# 12-Power.net
KiCad netlist of a schematic drawn in Altium Designer
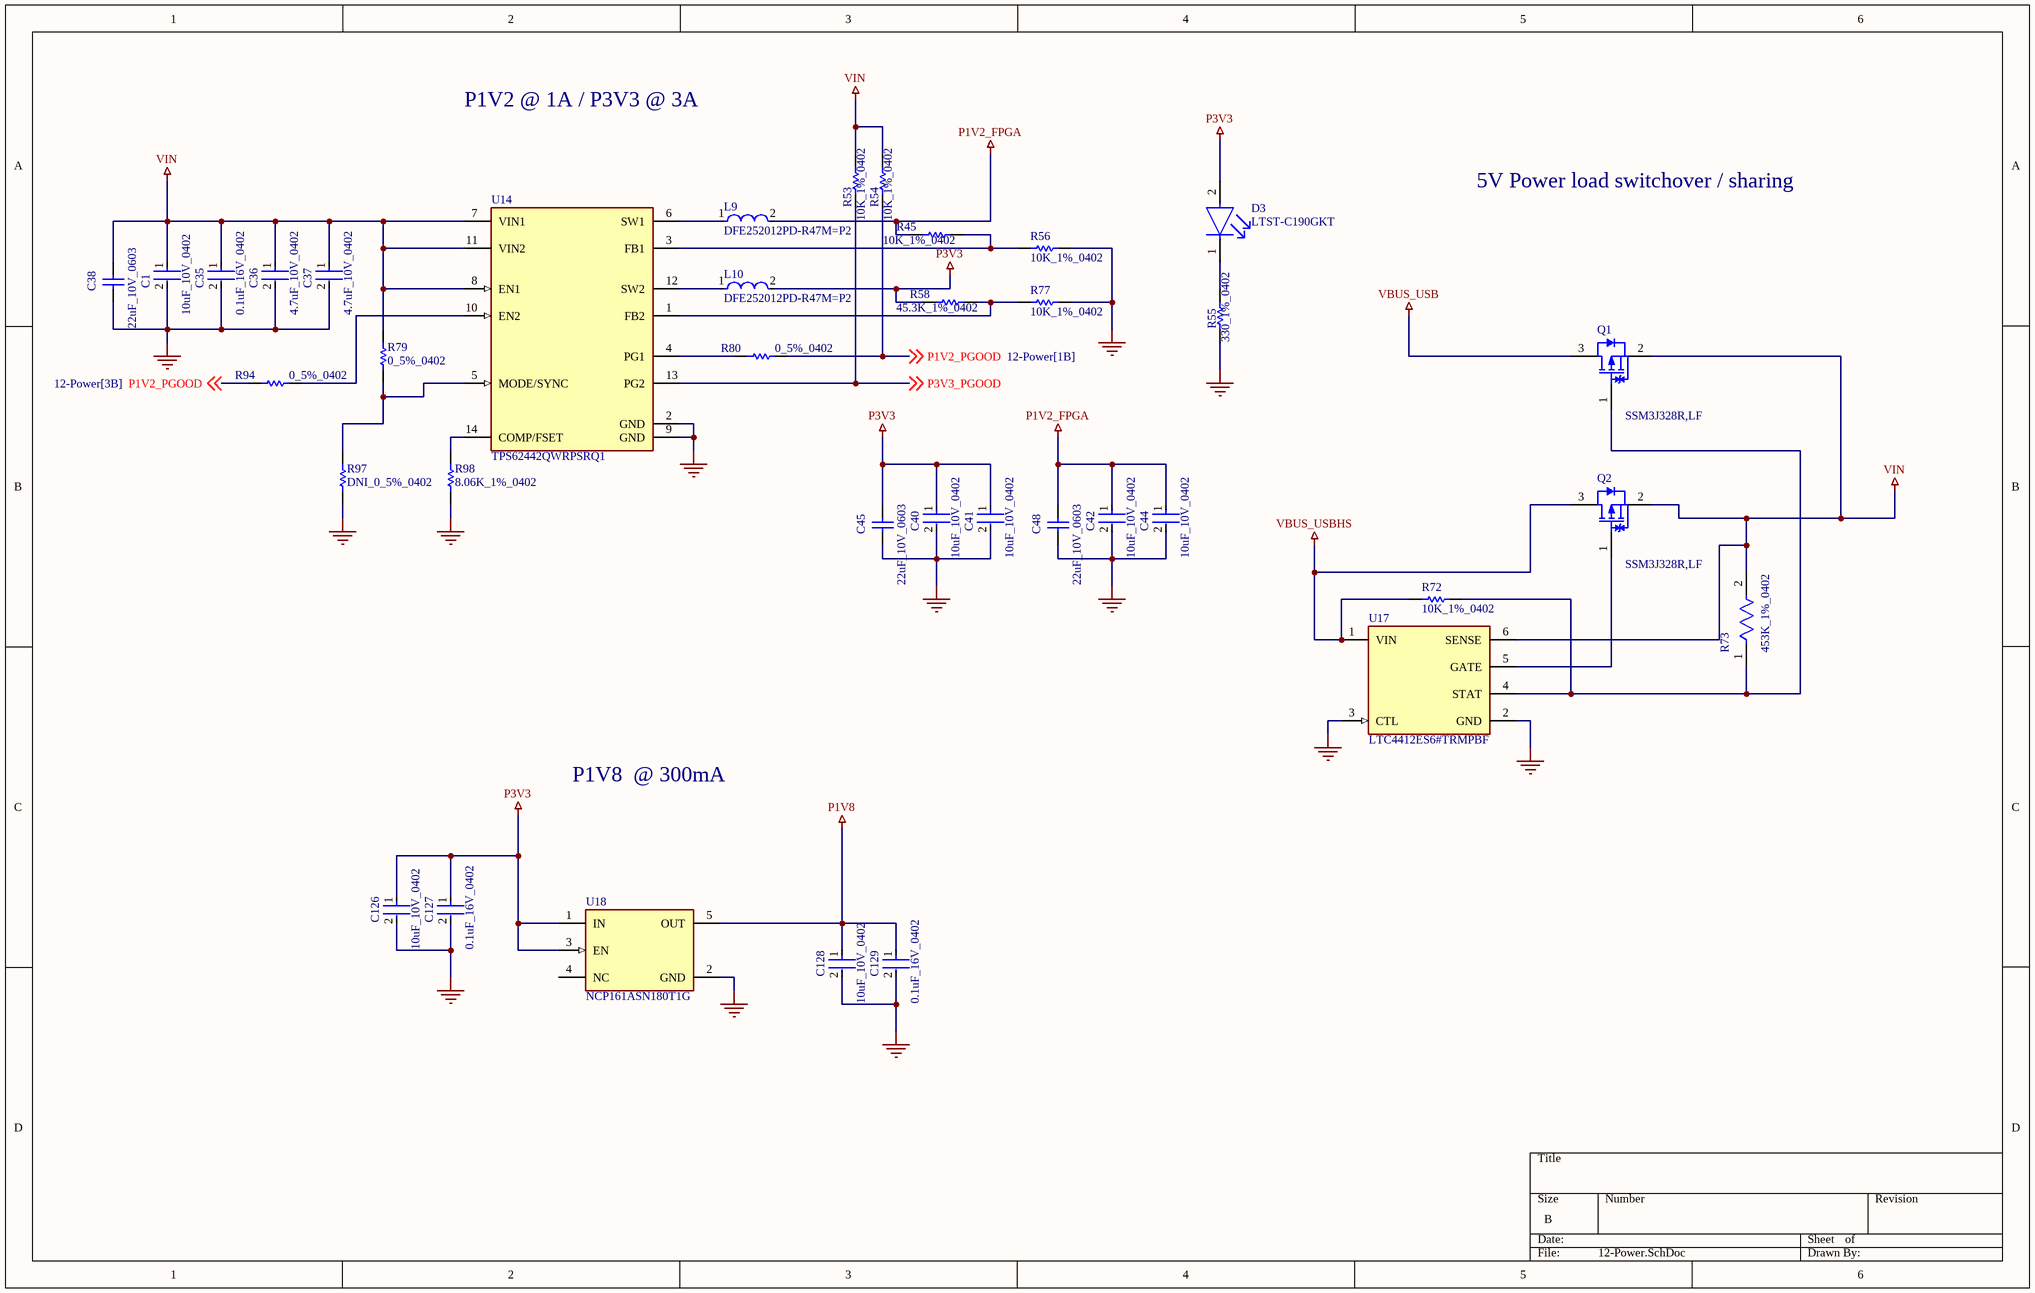
[diagram p0: 12-Power.SchDoc]

(export (version "E")
  (design (tool "Eeschema 10.0.6"))
  (components
    (comp (ref "C1")
      (value "10uF_10V_0402")
      (footprint "FP-CL05A106MP5NUNC-MFG")
      (description "CAP CER 10UF 10V X5R 0402")
      (fields
        (field (name "OCTOPART") "https://octopart.com/cl05a106mp5nunc-samsung-22457395")
        (field (name "TOLERANCE") "20%")
      )
      (libsource (lib "Altium Content Vault") (part "b4654b650e69147ec39a6b967a45e02"))
    )
    (comp (ref "C35")
      (value "0.1uF_16V_0402")
      (footprint "FP-C0402-BB-MFG")
      (description "CAP CER 0.1UF 16V 5% X7R 0402")
      (fields
        (field (name "MANUFACTURER") "Kemet")
        (field (name "MANUFACTURER PART NUMBER") "C0402C104J4RACTU")
      )
      (libsource (lib "Altium Content Vault") (part "b4654b650e69147ec39a6b967a45e02"))
    )
    (comp (ref "C36")
      (value "4.7uF_10V_0402")
      (footprint "FP-C1005-050-0_15-MFG")
      (description "CAP CER 4.7UF 10V X5R 0402")
      (fields (field (name "TOLERANCE") "10%"))
      (libsource (lib "Altium Content Vault") (part "b4654b650e69147ec39a6b967a45e02"))
    )
    (comp (ref "C37")
      (value "4.7uF_10V_0402")
      (footprint "FP-C1005-050-0_15-MFG")
      (description "CAP CER 4.7UF 10V X5R 0402")
      (fields (field (name "TOLERANCE") "10%"))
      (libsource (lib "Altium Content Vault") (part "b4654b650e69147ec39a6b967a45e02"))
    )
    (comp (ref "C38")
      (value "22uF_10V_0603")
      (footprint "CAPC1608X100X20ML10")
      (description "Chip Capacitor, 22 uF, +/- 20%, 10 V, -55 to 85 degC, 0603 (1608 Metric), RoHS, Tape and Reel")
      (fields (field (name "MANUFACTURER") "TDK") (field (name "TOLERANCE") "±20%"))
      (libsource (lib "Altium Content Vault") (part "CAP-NP-2"))
    )
    (comp (ref "C40")
      (value "10uF_10V_0402")
      (footprint "FP-CL05A106MP5NUNC-MFG")
      (description "CAP CER 10UF 10V X5R 0402")
      (fields
        (field (name "OCTOPART") "https://octopart.com/cl05a106mp5nunc-samsung-22457395")
        (field (name "TOLERANCE") "20%")
      )
      (libsource (lib "Altium Content Vault") (part "b4654b650e69147ec39a6b967a45e02"))
    )
    (comp (ref "C41")
      (value "10uF_10V_0402")
      (footprint "FP-CL05A106MP5NUNC-MFG")
      (description "CAP CER 10UF 10V X5R 0402")
      (fields
        (field (name "OCTOPART") "https://octopart.com/cl05a106mp5nunc-samsung-22457395")
        (field (name "TOLERANCE") "20%")
      )
      (libsource (lib "Altium Content Vault") (part "b4654b650e69147ec39a6b967a45e02"))
    )
    (comp (ref "C42")
      (value "10uF_10V_0402")
      (footprint "FP-CL05A106MP5NUNC-MFG")
      (description "CAP CER 10UF 10V X5R 0402")
      (fields
        (field (name "OCTOPART") "https://octopart.com/cl05a106mp5nunc-samsung-22457395")
        (field (name "TOLERANCE") "20%")
      )
      (libsource (lib "Altium Content Vault") (part "b4654b650e69147ec39a6b967a45e02"))
    )
    (comp (ref "C44")
      (value "10uF_10V_0402")
      (footprint "FP-CL05A106MP5NUNC-MFG")
      (description "CAP CER 10UF 10V X5R 0402")
      (fields
        (field (name "OCTOPART") "https://octopart.com/cl05a106mp5nunc-samsung-22457395")
        (field (name "TOLERANCE") "20%")
      )
      (libsource (lib "Altium Content Vault") (part "b4654b650e69147ec39a6b967a45e02"))
    )
    (comp (ref "C45")
      (value "22uF_10V_0603")
      (footprint "CAPC1608X100X20ML10")
      (description "Chip Capacitor, 22 uF, +/- 20%, 10 V, -55 to 85 degC, 0603 (1608 Metric), RoHS, Tape and Reel")
      (fields (field (name "MANUFACTURER") "TDK") (field (name "TOLERANCE") "±20%"))
      (libsource (lib "Altium Content Vault") (part "CAP-NP-2"))
    )
    (comp (ref "C48")
      (value "22uF_10V_0603")
      (footprint "CAPC1608X100X20ML10")
      (description "Chip Capacitor, 22 uF, +/- 20%, 10 V, -55 to 85 degC, 0603 (1608 Metric), RoHS, Tape and Reel")
      (fields (field (name "MANUFACTURER") "TDK") (field (name "TOLERANCE") "±20%"))
      (libsource (lib "Altium Content Vault") (part "CAP-NP-2"))
    )
    (comp (ref "C126")
      (value "10uF_10V_0402")
      (footprint "FP-CL05A106MP5NUNC-MFG")
      (description "CAP CER 10UF 10V X5R 0402")
      (fields
        (field (name "OCTOPART") "https://octopart.com/cl05a106mp5nunc-samsung-22457395")
        (field (name "TOLERANCE") "20%")
      )
      (libsource (lib "Altium Content Vault") (part "b4654b650e69147ec39a6b967a45e02"))
    )
    (comp (ref "C127")
      (value "0.1uF_16V_0402")
      (footprint "FP-C0402-BB-MFG")
      (description "CAP CER 0.1UF 16V 5% X7R 0402")
      (fields
        (field (name "MANUFACTURER") "Kemet")
        (field (name "MANUFACTURER PART NUMBER") "C0402C104J4RACTU")
      )
      (libsource (lib "Altium Content Vault") (part "b4654b650e69147ec39a6b967a45e02"))
    )
    (comp (ref "C128")
      (value "10uF_10V_0402")
      (footprint "FP-CL05A106MP5NUNC-MFG")
      (description "CAP CER 10UF 10V X5R 0402")
      (fields
        (field (name "OCTOPART") "https://octopart.com/cl05a106mp5nunc-samsung-22457395")
        (field (name "TOLERANCE") "20%")
      )
      (libsource (lib "Altium Content Vault") (part "b4654b650e69147ec39a6b967a45e02"))
    )
    (comp (ref "C129")
      (value "0.1uF_16V_0402")
      (footprint "FP-C0402-BB-MFG")
      (description "CAP CER 0.1UF 16V 5% X7R 0402")
      (fields
        (field (name "MANUFACTURER") "Kemet")
        (field (name "MANUFACTURER PART NUMBER") "C0402C104J4RACTU")
      )
      (libsource (lib "Altium Content Vault") (part "b4654b650e69147ec39a6b967a45e02"))
    )
    (comp (ref "D3")
      (value "LTST-C190GKT")
      (footprint "FP-LTST-C190GKT-MFG")
      (description "LED GREEN CLEAR CHIP SMD")
      (fields (field (name "VOLTAGE") "2V"))
      (libsource (lib "Altium Content Vault") (part "8706943c75ba83719d021d2fdc84c58"))
    )
    (comp (ref "L9")
      (value "DFE252012PD-R47M=P2")
      (footprint "FP-DFE252012C-IPC_A")
      (description "Shielded Wirewound Inductor 0.47uH 20% 4000mA 0.027Ω 1008 (2520)")
      (libsource (lib "Altium Content Vault") (part "725321dda6339637d4d059423bc1c3c"))
    )
    (comp (ref "L10")
      (value "DFE252012PD-R47M=P2")
      (footprint "FP-DFE252012C-IPC_A")
      (description "Shielded Wirewound Inductor 0.47uH 20% 4000mA 0.027Ω 1008 (2520)")
      (libsource (lib "Altium Content Vault") (part "725321dda6339637d4d059423bc1c3c"))
    )
    (comp (ref "Q1")
      (value "SSM3J328R,LF")
      (footprint "TOSH-SOT-23F_V")
      (fields (field (name "MANUFACTURER") "Toshiba"))
      (libsource (lib "Altium Content Vault") (part "PEMOS-GSD-3_C"))
    )
    (comp (ref "Q2")
      (value "SSM3J328R,LF")
      (footprint "TOSH-SOT-23F_V")
      (fields (field (name "MANUFACTURER") "Toshiba"))
      (libsource (lib "Altium Content Vault") (part "PEMOS-GSD-3_C"))
    )
    (comp (ref "R45")
      (value "10K_1%_0402")
      (footprint "RESC1005X40X25NL10T10")
      (fields (field (name "MANUFACTURER") "Bourns") (field (name "PART NUMBER") "CR0402-FX-1002GLF"))
      (libsource (lib "Altium Content Vault") (part "RES"))
    )
    (comp (ref "R53")
      (value "10K_1%_0402")
      (footprint "RESC1005X40X25NL10T10")
      (fields (field (name "MANUFACTURER") "Bourns") (field (name "PART NUMBER") "CR0402-FX-1002GLF"))
      (libsource (lib "Altium Content Vault") (part "RES"))
    )
    (comp (ref "R54")
      (value "10K_1%_0402")
      (footprint "RESC1005X40X25NL10T10")
      (fields (field (name "MANUFACTURER") "Bourns") (field (name "PART NUMBER") "CR0402-FX-1002GLF"))
      (libsource (lib "Altium Content Vault") (part "RES"))
    )
    (comp (ref "R55")
      (value "330_1%_0402")
      (footprint "RESC1005X40X25NL10T10")
      (fields (field (name "MANUFACTURER") "Panasonic") (field (name "PART NUMBER") "ERA-2AED331X"))
      (libsource (lib "Altium Content Vault") (part "RES"))
    )
    (comp (ref "R56")
      (value "10K_1%_0402")
      (footprint "RESC1005X40X25NL10T10")
      (fields (field (name "MANUFACTURER") "Bourns") (field (name "PART NUMBER") "CR0402-FX-1002GLF"))
      (libsource (lib "Altium Content Vault") (part "RES"))
    )
    (comp (ref "R58")
      (value "45.3K_1%_0402")
      (footprint "RESC0402(1005)_L")
      (description "45K3 0.063W 1% 0402 (1005 Metric)  SMD")
      (fields (field (name "TOLERANCE") "1 %") (field (name "POWER") "0.063 W"))
      (libsource (lib "Altium Content Vault") (part "RES"))
    )
    (comp (ref "R72")
      (value "10K_1%_0402")
      (footprint "RESC1005X40X25NL10T10")
      (fields (field (name "MANUFACTURER") "Bourns") (field (name "PART NUMBER") "CR0402-FX-1002GLF"))
      (libsource (lib "Altium Content Vault") (part "RES"))
    )
    (comp (ref "R73")
      (value "453K_1%_0402")
      (footprint "FP-RC1005-IPC_B")
      (description "Res Thick Film 0402 453kΩ 1% 0.063W ±100ppm/°C Molded SMD T/R")
      (fields (field (name "TOLERANCE") "1%"))
      (libsource (lib "Altium Content Vault") (part "1029c3af85768c4190bb7ad29bc67b5"))
    )
    (comp (ref "R77")
      (value "10K_1%_0402")
      (footprint "RESC1005X40X25NL10T10")
      (fields (field (name "MANUFACTURER") "Bourns") (field (name "PART NUMBER") "CR0402-FX-1002GLF"))
      (libsource (lib "Altium Content Vault") (part "RES"))
    )
    (comp (ref "R79")
      (value "0_5%_0402")
      (footprint "RESC1005X40X25NL05T10")
      (fields (field (name "MANUFACTURER") "Panasonic") (field (name "PART NUMBER") "ERJ-U020R00X"))
      (libsource (lib "Altium Content Vault") (part "RES"))
    )
    (comp (ref "R80")
      (value "0_5%_0402")
      (footprint "RESC1005X40X25NL05T10")
      (fields (field (name "MANUFACTURER") "Panasonic") (field (name "PART NUMBER") "ERJ-U020R00X"))
      (libsource (lib "Altium Content Vault") (part "RES"))
    )
    (comp (ref "R94")
      (value "0_5%_0402")
      (footprint "RESC1005X40X25NL05T10")
      (fields (field (name "MANUFACTURER") "Panasonic") (field (name "PART NUMBER") "ERJ-U020R00X"))
      (libsource (lib "Altium Content Vault") (part "RES"))
    )
    (comp (ref "R97")
      (value "DNI_0_5%_0402")
      (footprint "RESC1005X40X25NL05T10")
      (fields (field (name "MANUFACTURER") "Panasonic") (field (name "PART NUMBER") "ERJ-U020R00X"))
      (libsource (lib "Altium Content Vault") (part "RES"))
    )
    (comp (ref "R98")
      (value "8.06K_1%_0402")
      (footprint "RESC1005X40X25ML05T05")
      (description "Chip Resistor, 8.06 KOhm, +/- 1%, 63 mW, -55 to 155 degC, 0402 (1005 Metric), RoHS, Tape and Reel")
      (fields (field (name "PARTNUMBER") "CRCW04028K06FKED") (field (name "TOLERANCE") "1%"))
      (libsource (lib "Altium Content Vault") (part "RES-2"))
    )
    (comp (ref "U14")
      (value "TPS62442QWRPSRQ1")
      (footprint "FP-RQR0014A-MFG")
      (description "Adjustable-Frequency Dual Step-Down Converter, 2.7-6V VIN, 0.6-5.5V 2A VOUT, VQFN-HR14")
      (libsource (lib "Altium Content Vault") (part "72c5b9bb22caeb688b1070b758806aa"))
    )
    (comp (ref "U17")
      (value "LTC4412ES6#TRMPBF")
      (footprint "FP-S6-6-05-08-1636-IPC_C")
      (description "IC OR CTRLR SRC SELECT TSOT23-6")
      (libsource (lib "Altium Content Vault") (part "07cb0f4431a3a7488227ca1baae77bb"))
    )
    (comp (ref "U18")
      (value "NCP161ASN180T1G")
      (footprint "FP-527AH-MFG")
      (libsource (lib "Altium Content Vault") (part "07e51adf658dd7550fcbd1980b41b01"))
    )
  )
  (nets
    (net (code "1") (name "GND") (class "Default")
      (node (ref "C1") (pin "2") (pinfunction "2_2") (pintype "passive"))
      (node (ref "C126") (pin "2") (pinfunction "2_2") (pintype "passive"))
      (node (ref "C127") (pin "2") (pinfunction "2_2") (pintype "passive"))
      (node (ref "C128") (pin "2") (pinfunction "2_2") (pintype "passive"))
      (node (ref "C129") (pin "2") (pinfunction "2_2") (pintype "passive"))
      (node (ref "C35") (pin "2") (pinfunction "2_2") (pintype "passive"))
      (node (ref "C36") (pin "2") (pinfunction "2_2") (pintype "passive"))
      (node (ref "C37") (pin "2") (pinfunction "2_2") (pintype "passive"))
      (node (ref "C38") (pin "1") (pinfunction "1_1") (pintype "passive"))
      (node (ref "C40") (pin "2") (pinfunction "2_2") (pintype "passive"))
      (node (ref "C41") (pin "2") (pinfunction "2_2") (pintype "passive"))
      (node (ref "C42") (pin "2") (pinfunction "2_2") (pintype "passive"))
      (node (ref "C44") (pin "2") (pinfunction "2_2") (pintype "passive"))
      (node (ref "C45") (pin "1") (pinfunction "1_1") (pintype "passive"))
      (node (ref "C48") (pin "1") (pinfunction "1_1") (pintype "passive"))
      (node (ref "R55") (pin "1") (pinfunction "1_1") (pintype "passive"))
      (node (ref "R56") (pin "1") (pinfunction "1_1") (pintype "passive"))
      (node (ref "R77") (pin "1") (pinfunction "1_1") (pintype "passive"))
      (node (ref "R97") (pin "1") (pinfunction "1_1") (pintype "passive"))
      (node (ref "R98") (pin "1") (pinfunction "1_1") (pintype "passive"))
      (node (ref "U14") (pin "2") (pinfunction "GND_2") (pintype "power_in"))
      (node (ref "U14") (pin "9") (pinfunction "GND_9") (pintype "power_in"))
      (node (ref "U17") (pin "2") (pinfunction "GND_2") (pintype "power_in"))
      (node (ref "U17") (pin "3") (pinfunction "CTL_3") (pintype "input"))
      (node (ref "U18") (pin "2") (pinfunction "GND_2") (pintype "power_in"))
    )
    (net (code "2") (name "Net-(D3-C)") (class "Default")
      (node (ref "D3") (pin "1") (pinfunction "C_1") (pintype "passive"))
      (node (ref "R55") (pin "2") (pinfunction "2_2") (pintype "passive"))
    )
    (net (code "3") (name "Net-(Q1-G)") (class "Default")
      (node (ref "Q1") (pin "1") (pinfunction "G_1") (pintype "passive"))
      (node (ref "R72") (pin "2") (pinfunction "2_2") (pintype "passive"))
      (node (ref "R73") (pin "1") (pinfunction "1_1") (pintype "passive"))
      (node (ref "U17") (pin "4") (pinfunction "STAT_4") (pintype "open_collector"))
    )
    (net (code "4") (name "Net-(Q2-G)") (class "Default")
      (node (ref "Q2") (pin "1") (pinfunction "G_1") (pintype "passive"))
      (node (ref "U17") (pin "5") (pinfunction "GATE_5") (pintype "passive"))
    )
    (net (code "5") (name "Net-(U14-COMP{slash}FSET)") (class "Default")
      (node (ref "R98") (pin "2") (pinfunction "2_2") (pintype "passive"))
      (node (ref "U14") (pin "14") (pinfunction "COMP/FSET_14") (pintype "passive"))
    )
    (net (code "6") (name "Net-(U14-EN2)") (class "Default")
      (node (ref "R94") (pin "2") (pinfunction "2_2") (pintype "passive"))
      (node (ref "U14") (pin "10") (pinfunction "EN2_10") (pintype "input"))
    )
    (net (code "7") (name "Net-(U14-FB1)") (class "Default")
      (node (ref "R45") (pin "1") (pinfunction "1_1") (pintype "passive"))
      (node (ref "R56") (pin "2") (pinfunction "2_2") (pintype "passive"))
      (node (ref "U14") (pin "3") (pinfunction "FB1_3") (pintype "passive"))
    )
    (net (code "8") (name "Net-(U14-FB2)") (class "Default")
      (node (ref "R58") (pin "2") (pinfunction "2_2") (pintype "passive"))
      (node (ref "R77") (pin "2") (pinfunction "2_2") (pintype "passive"))
      (node (ref "U14") (pin "1") (pinfunction "FB2_1") (pintype "passive"))
    )
    (net (code "9") (name "Net-(U14-MODE{slash}SYNC)") (class "Default")
      (node (ref "R79") (pin "1") (pinfunction "1_1") (pintype "passive"))
      (node (ref "R97") (pin "2") (pinfunction "2_2") (pintype "passive"))
      (node (ref "U14") (pin "5") (pinfunction "MODE/SYNC_5") (pintype "input"))
    )
    (net (code "10") (name "Net-(U14-PG1)") (class "Default")
      (node (ref "R80") (pin "1") (pinfunction "1_1") (pintype "passive"))
      (node (ref "U14") (pin "4") (pinfunction "PG1_4") (pintype "open_collector"))
    )
    (net (code "11") (name "Net-(U14-SW1)") (class "Default")
      (node (ref "L9") (pin "1") (pinfunction "1_1") (pintype "passive"))
      (node (ref "U14") (pin "6") (pinfunction "SW1_6") (pintype "passive"))
    )
    (net (code "12") (name "Net-(U14-SW2)") (class "Default")
      (node (ref "L10") (pin "1") (pinfunction "1_1") (pintype "passive"))
      (node (ref "U14") (pin "12") (pinfunction "SW2_12") (pintype "passive"))
    )
    (net (code "13") (name "P1V2_FPGA") (class "Default")
      (node (ref "C42") (pin "1") (pinfunction "1_1") (pintype "passive"))
      (node (ref "C44") (pin "1") (pinfunction "1_1") (pintype "passive"))
      (node (ref "C48") (pin "2") (pinfunction "2_2") (pintype "passive"))
      (node (ref "L9") (pin "2") (pinfunction "2_2") (pintype "passive"))
      (node (ref "R45") (pin "2") (pinfunction "2_2") (pintype "passive"))
    )
    (net (code "14") (name "P1V2_PGOOD") (class "Default")
      (node (ref "R54") (pin "1") (pinfunction "1_1") (pintype "passive"))
      (node (ref "R80") (pin "2") (pinfunction "2_2") (pintype "passive"))
      (node (ref "R94") (pin "1") (pinfunction "1_1") (pintype "passive"))
    )
    (net (code "15") (name "P1V8") (class "Default")
      (node (ref "C128") (pin "1") (pinfunction "1_1") (pintype "passive"))
      (node (ref "C129") (pin "1") (pinfunction "1_1") (pintype "passive"))
      (node (ref "U18") (pin "5") (pinfunction "OUT_5") (pintype "passive"))
    )
    (net (code "16") (name "P3V3") (class "Default")
      (node (ref "C126") (pin "1") (pinfunction "1_1") (pintype "passive"))
      (node (ref "C127") (pin "1") (pinfunction "1_1") (pintype "passive"))
      (node (ref "C40") (pin "1") (pinfunction "1_1") (pintype "passive"))
      (node (ref "C41") (pin "1") (pinfunction "1_1") (pintype "passive"))
      (node (ref "C45") (pin "2") (pinfunction "2_2") (pintype "passive"))
      (node (ref "D3") (pin "2") (pinfunction "A_2") (pintype "passive"))
      (node (ref "L10") (pin "2") (pinfunction "2_2") (pintype "passive"))
      (node (ref "R58") (pin "1") (pinfunction "1_1") (pintype "passive"))
      (node (ref "U18") (pin "1") (pinfunction "IN_1") (pintype "power_in"))
      (node (ref "U18") (pin "3") (pinfunction "EN_3") (pintype "input"))
    )
    (net (code "17") (name "P3V3_PGOOD") (class "Default")
      (node (ref "R53") (pin "1") (pinfunction "1_1") (pintype "passive"))
      (node (ref "U14") (pin "13") (pinfunction "PG2_13") (pintype "open_collector"))
    )
    (net (code "18") (name "VBUS_USB") (class "Default")
      (node (ref "Q1") (pin "3") (pinfunction "D_3") (pintype "passive"))
    )
    (net (code "19") (name "VBUS_USBHS") (class "Default")
      (node (ref "Q2") (pin "3") (pinfunction "D_3") (pintype "passive"))
      (node (ref "R72") (pin "1") (pinfunction "1_1") (pintype "passive"))
      (node (ref "U17") (pin "1") (pinfunction "VIN_1") (pintype "power_in"))
    )
    (net (code "20") (name "VIN") (class "Default")
      (node (ref "C1") (pin "1") (pinfunction "1_1") (pintype "passive"))
      (node (ref "C35") (pin "1") (pinfunction "1_1") (pintype "passive"))
      (node (ref "C36") (pin "1") (pinfunction "1_1") (pintype "passive"))
      (node (ref "C37") (pin "1") (pinfunction "1_1") (pintype "passive"))
      (node (ref "C38") (pin "2") (pinfunction "2_2") (pintype "passive"))
      (node (ref "Q1") (pin "2") (pinfunction "S_2") (pintype "passive"))
      (node (ref "Q2") (pin "2") (pinfunction "S_2") (pintype "passive"))
      (node (ref "R53") (pin "2") (pinfunction "2_2") (pintype "passive"))
      (node (ref "R54") (pin "2") (pinfunction "2_2") (pintype "passive"))
      (node (ref "R73") (pin "2") (pinfunction "2_2") (pintype "passive"))
      (node (ref "R79") (pin "2") (pinfunction "2_2") (pintype "passive"))
      (node (ref "U14") (pin "11") (pinfunction "VIN2_11") (pintype "power_in"))
      (node (ref "U14") (pin "7") (pinfunction "VIN1_7") (pintype "power_in"))
      (node (ref "U14") (pin "8") (pinfunction "EN1_8") (pintype "input"))
      (node (ref "U17") (pin "6") (pinfunction "SENSE_6") (pintype "passive"))
    )
    (net (code "21") (name "unconnected-(U18-NC-Pad4)") (class "Default")
      (node (ref "U18") (pin "4") (pinfunction "NC_4") (pintype "passive"))
    )
  )
)
